# TSSOP-20.net
KiCad netlist of a schematic drawn in EAGLE
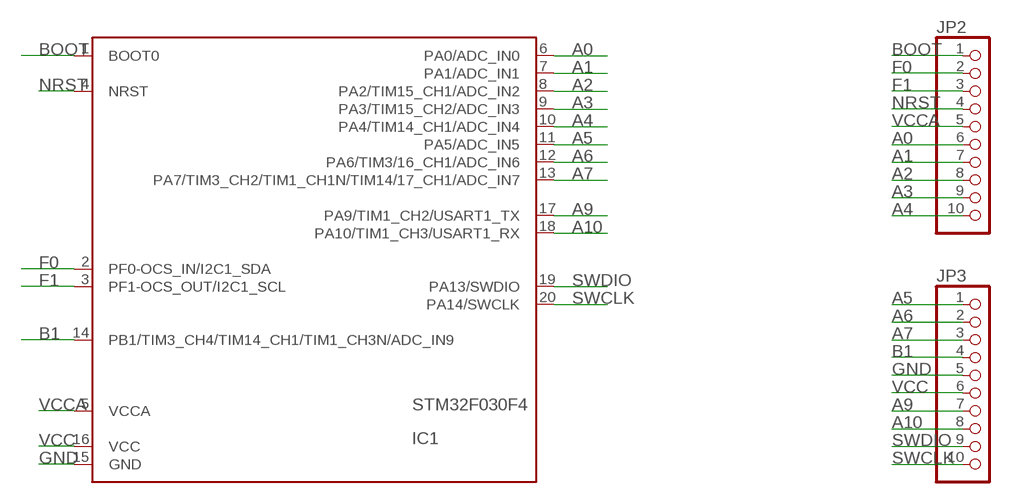
[diagram p0: schematic, sheet 1]

(export (version "E")
  (design (tool "Eeschema 10.0.6"))
  (components
    (comp (ref "IC1")
      (value "STM32F030F4")
      (footprint "eagle-import:TSSOP20")
      (libsource (lib "eagle-import") (part "STM32F030F4"))
    )
    (comp (ref "JP2")
      (value "PINHD-1X10")
      (footprint "eagle-import:1X10")
      (libsource (lib "eagle-import") (part "PINHD-1X10"))
    )
    (comp (ref "JP3")
      (value "PINHD-1X10")
      (footprint "eagle-import:1X10")
      (libsource (lib "eagle-import") (part "PINHD-1X10"))
    )
  )
  (nets
    (net (code "1") (name "/A0") (class "Default")
      (node (ref "IC1") (pin "6") (pinfunction "PA0/ADC_IN0_6") (pintype "bidirectional"))
      (node (ref "JP2") (pin "6") (pinfunction "6_6") (pintype "passive"))
    )
    (net (code "2") (name "/A1") (class "Default")
      (node (ref "IC1") (pin "7") (pinfunction "PA1/ADC_IN1_7") (pintype "bidirectional"))
      (node (ref "JP2") (pin "7") (pinfunction "7_7") (pintype "passive"))
    )
    (net (code "3") (name "/A2") (class "Default")
      (node (ref "IC1") (pin "8") (pinfunction "PA2/TIM15_CH1/ADC_IN2_8") (pintype "bidirectional"))
      (node (ref "JP2") (pin "8") (pinfunction "8_8") (pintype "passive"))
    )
    (net (code "4") (name "/A3") (class "Default")
      (node (ref "IC1") (pin "9") (pinfunction "PA3/TIM15_CH2/ADC_IN3_9") (pintype "bidirectional"))
      (node (ref "JP2") (pin "9") (pinfunction "9_9") (pintype "passive"))
    )
    (net (code "5") (name "/A4") (class "Default")
      (node (ref "IC1") (pin "10") (pinfunction "PA4/TIM14_CH1/ADC_IN4_10") (pintype "bidirectional"))
      (node (ref "JP2") (pin "10") (pinfunction "10_10") (pintype "passive"))
    )
    (net (code "6") (name "/A5") (class "Default")
      (node (ref "IC1") (pin "11") (pinfunction "PA5/ADC_IN5_11") (pintype "bidirectional"))
      (node (ref "JP3") (pin "1") (pinfunction "1_1") (pintype "passive"))
    )
    (net (code "7") (name "/A6") (class "Default")
      (node (ref "IC1") (pin "12") (pinfunction "PA6/TIM3/16_CH1/ADC_IN6_12") (pintype "bidirectional"))
      (node (ref "JP3") (pin "2") (pinfunction "2_2") (pintype "passive"))
    )
    (net (code "8") (name "/A7") (class "Default")
      (node (ref "IC1") (pin "13") (pinfunction "PA7/TIM3_CH2/TIM1_CH1N/TIM14/17_CH1/ADC_IN7_13") (pintype "bidirectional"))
      (node (ref "JP3") (pin "3") (pinfunction "3_3") (pintype "passive"))
    )
    (net (code "9") (name "/A9") (class "Default")
      (node (ref "IC1") (pin "17") (pinfunction "PA9/TIM1_CH2/USART1_TX_17") (pintype "bidirectional"))
      (node (ref "JP3") (pin "7") (pinfunction "7_7") (pintype "passive"))
    )
    (net (code "10") (name "/A10") (class "Default")
      (node (ref "IC1") (pin "18") (pinfunction "PA10/TIM1_CH3/USART1_RX_18") (pintype "bidirectional"))
      (node (ref "JP3") (pin "8") (pinfunction "8_8") (pintype "passive"))
    )
    (net (code "11") (name "/B1") (class "Default")
      (node (ref "IC1") (pin "14") (pinfunction "PB1/TIM3_CH4/TIM14_CH1/TIM1_CH3N/ADC_IN9_14") (pintype "bidirectional"))
      (node (ref "JP3") (pin "4") (pinfunction "4_4") (pintype "passive"))
    )
    (net (code "12") (name "/BOOT") (class "Default")
      (node (ref "IC1") (pin "1") (pinfunction "BOOT0_1") (pintype "bidirectional"))
      (node (ref "JP2") (pin "1") (pinfunction "1_1") (pintype "passive"))
    )
    (net (code "13") (name "/F0") (class "Default")
      (node (ref "IC1") (pin "2") (pinfunction "PF0-OCS_IN/I2C1_SDA_2") (pintype "bidirectional"))
      (node (ref "JP2") (pin "2") (pinfunction "2_2") (pintype "passive"))
    )
    (net (code "14") (name "/F1") (class "Default")
      (node (ref "IC1") (pin "3") (pinfunction "PF1-OCS_OUT/I2C1_SCL_3") (pintype "bidirectional"))
      (node (ref "JP2") (pin "3") (pinfunction "3_3") (pintype "passive"))
    )
    (net (code "15") (name "/GND") (class "Default")
      (node (ref "IC1") (pin "15") (pinfunction "GND_15") (pintype "power_in"))
      (node (ref "JP3") (pin "5") (pinfunction "5_5") (pintype "passive"))
    )
    (net (code "16") (name "/NRST") (class "Default")
      (node (ref "IC1") (pin "4") (pinfunction "NRST_4") (pintype "bidirectional"))
      (node (ref "JP2") (pin "4") (pinfunction "4_4") (pintype "passive"))
    )
    (net (code "17") (name "/SWCLK") (class "Default")
      (node (ref "IC1") (pin "20") (pinfunction "PA14/SWCLK_20") (pintype "bidirectional"))
      (node (ref "JP3") (pin "10") (pinfunction "10_10") (pintype "passive"))
    )
    (net (code "18") (name "/SWDIO") (class "Default")
      (node (ref "IC1") (pin "19") (pinfunction "PA13/SWDIO_19") (pintype "bidirectional"))
      (node (ref "JP3") (pin "9") (pinfunction "9_9") (pintype "passive"))
    )
    (net (code "19") (name "/VCC") (class "Default")
      (node (ref "IC1") (pin "16") (pinfunction "VCC_16") (pintype "power_in"))
      (node (ref "JP3") (pin "6") (pinfunction "6_6") (pintype "passive"))
    )
    (net (code "20") (name "/VCCA") (class "Default")
      (node (ref "IC1") (pin "5") (pinfunction "VCCA_5") (pintype "power_in"))
      (node (ref "JP2") (pin "5") (pinfunction "5_5") (pintype "passive"))
    )
  )
)
